# DoorBellRepeater.net
KiCad netlist of a schematic drawn in EAGLE
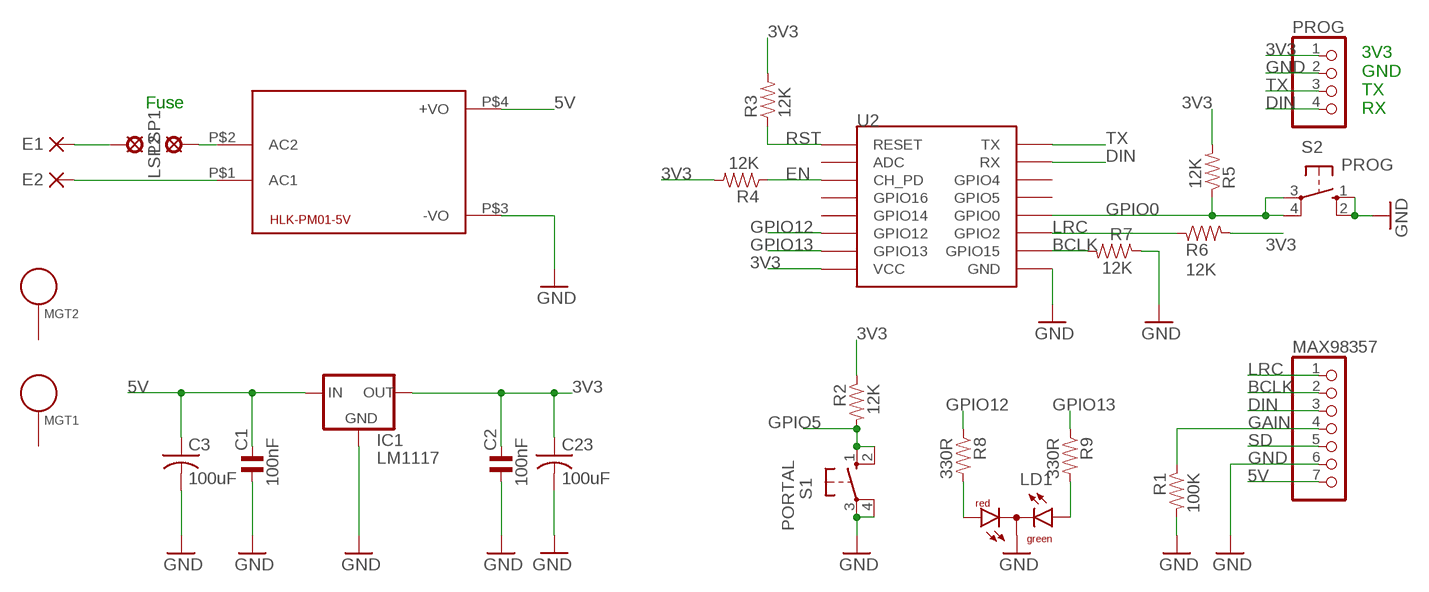
[diagram p0: schematic, sheet 1]

(export (version "E")
  (design (tool "Eeschema 10.0.6"))
  (components
    (comp (ref "C1")
      (value "100nF")
      (footprint "eagle-import:C0805MP")
      (libsource (lib "eagle-import") (part "C_0805MP"))
    )
    (comp (ref "C2")
      (value "100nF")
      (footprint "eagle-import:C0805MP")
      (libsource (lib "eagle-import") (part "C_0805MP"))
    )
    (comp (ref "C3")
      (value "100uF")
      (footprint "eagle-import:C0805K")
      (libsource (lib "eagle-import") (part "C-USC0805K"))
    )
    (comp (ref "C23")
      (value "100uF")
      (footprint "eagle-import:C0805K")
      (libsource (lib "eagle-import") (part "C-USC0805K"))
    )
    (comp (ref "E1")
      (value "PAD-0460S-S")
      (footprint "eagle-import:0460S-S")
      (libsource (lib "eagle-import") (part "PAD-0460S-S"))
    )
    (comp (ref "E2")
      (value "PAD-0460S-S")
      (footprint "eagle-import:0460S-S")
      (libsource (lib "eagle-import") (part "PAD-0460S-S"))
    )
    (comp (ref "HLK-PM01-5V")
      (value "HLK-PM013W")
      (footprint "eagle-import:HLK-PM01")
      (libsource (lib "eagle-import") (part "HLK-PM013W"))
    )
    (comp (ref "IC1")
      (value "LM1117")
      (footprint "eagle-import:SOT223")
      (libsource (lib "eagle-import") (part "LM1117"))
    )
    (comp (ref "LD1")
      (value "DUOLED-RG-C")
      (footprint "eagle-import:DUOLED-C-5MM")
      (libsource (lib "eagle-import") (part "DUOLED-RG-C"))
    )
    (comp (ref "LSP1")
      (value "LSP10")
      (footprint "eagle-import:LSP10")
      (libsource (lib "eagle-import") (part "LSP10"))
    )
    (comp (ref "LSP2")
      (value "LSP10")
      (footprint "eagle-import:LSP10")
      (libsource (lib "eagle-import") (part "LSP10"))
    )
    (comp (ref "MAX98357")
      (value "PINHD-1X7")
      (footprint "eagle-import:1X07")
      (libsource (lib "eagle-import") (part "PINHD-1X7"))
    )
    (comp (ref "MGT1")
      (value "MOUNTING_HOLE")
      (footprint "eagle-import:BEAGLEBONEBLACK_MOUNTING_HOLE")
      (libsource (lib "eagle-import") (part "MOUNTING_HOLE"))
    )
    (comp (ref "MGT2")
      (value "MOUNTING_HOLE")
      (footprint "eagle-import:BEAGLEBONEBLACK_MOUNTING_HOLE")
      (libsource (lib "eagle-import") (part "MOUNTING_HOLE"))
    )
    (comp (ref "PROG")
      (value "PINHD-1X4")
      (footprint "eagle-import:1X04")
      (libsource (lib "eagle-import") (part "PINHD-1X4"))
    )
    (comp (ref "R1")
      (value "100K")
      (footprint "eagle-import:0805_RES")
      (libsource (lib "eagle-import") (part "RESISTOR0805_RES"))
    )
    (comp (ref "R2")
      (value "12K")
      (footprint "eagle-import:0805_RES")
      (libsource (lib "eagle-import") (part "RESISTOR0805_RES"))
    )
    (comp (ref "R3")
      (value "12K")
      (footprint "eagle-import:0805_RES")
      (libsource (lib "eagle-import") (part "RESISTOR0805_RES"))
    )
    (comp (ref "R4")
      (value "12K")
      (footprint "eagle-import:0805_RES")
      (libsource (lib "eagle-import") (part "RESISTOR0805_RES"))
    )
    (comp (ref "R5")
      (value "12K")
      (footprint "eagle-import:0805_RES")
      (libsource (lib "eagle-import") (part "RESISTOR0805_RES"))
    )
    (comp (ref "R6")
      (value "12K")
      (footprint "eagle-import:0805_RES")
      (libsource (lib "eagle-import") (part "RESISTOR0805_RES"))
    )
    (comp (ref "R7")
      (value "12K")
      (footprint "eagle-import:0805_RES")
      (libsource (lib "eagle-import") (part "RESISTOR0805_RES"))
    )
    (comp (ref "R8")
      (value "330R")
      (footprint "eagle-import:0805_RES")
      (libsource (lib "eagle-import") (part "RESISTOR0805_RES"))
    )
    (comp (ref "R9")
      (value "330R")
      (footprint "eagle-import:0805_RES")
      (libsource (lib "eagle-import") (part "RESISTOR0805_RES"))
    )
    (comp (ref "S1")
      (value "PORTAL")
      (footprint "eagle-import:B3F-10XX")
      (fields (field (name "MPN") "B3F-1000"))
      (libsource (lib "eagle-import") (part "10-XX"))
    )
    (comp (ref "S2")
      (value "PROG")
      (footprint "eagle-import:B3F-10XX")
      (fields (field (name "MPN") "B3F-1000"))
      (libsource (lib "eagle-import") (part "10-XX"))
    )
    (comp (ref "U2")
      (value "ESP12")
      (footprint "eagle-import:ESP12")
      (libsource (lib "eagle-import") (part "ESP12"))
    )
  )
  (nets
    (net (code "1") (name "/3V3") (class "Default")
      (node (ref "C2") (pin "2") (pinfunction "2_2") (pintype "passive"))
      (node (ref "C23") (pin "1") (pinfunction "1_1") (pintype "passive"))
      (node (ref "IC1") (pin "2") (pinfunction "OUT_2") (pintype "passive"))
      (node (ref "PROG") (pin "1") (pinfunction "1_1") (pintype "passive"))
      (node (ref "R2") (pin "1") (pinfunction "1_1") (pintype "passive"))
      (node (ref "R3") (pin "2") (pinfunction "2_2") (pintype "passive"))
      (node (ref "R4") (pin "2") (pinfunction "2_2") (pintype "passive"))
      (node (ref "R5") (pin "2") (pinfunction "2_2") (pintype "passive"))
      (node (ref "R6") (pin "2") (pinfunction "2_2") (pintype "passive"))
      (node (ref "U2") (pin "VCC") (pinfunction "VCC_VCC") (pintype "bidirectional"))
    )
    (net (code "2") (name "/5V") (class "Default")
      (node (ref "C1") (pin "2") (pinfunction "2_2") (pintype "passive"))
      (node (ref "C3") (pin "1") (pinfunction "1_1") (pintype "passive"))
      (node (ref "HLK-PM01-5V") (pin "P$4") (pinfunction "+VO_P$4") (pintype "bidirectional"))
      (node (ref "IC1") (pin "3") (pinfunction "IN_3") (pintype "input"))
      (node (ref "MAX98357") (pin "7") (pinfunction "7_7") (pintype "passive"))
    )
    (net (code "3") (name "/BCLK") (class "Default")
      (node (ref "MAX98357") (pin "2") (pinfunction "2_2") (pintype "passive"))
      (node (ref "R7") (pin "2") (pinfunction "2_2") (pintype "passive"))
      (node (ref "U2") (pin "GPIO15") (pinfunction "GPIO15_GPIO15") (pintype "bidirectional"))
    )
    (net (code "4") (name "/DIN") (class "Default")
      (node (ref "MAX98357") (pin "3") (pinfunction "3_3") (pintype "passive"))
      (node (ref "PROG") (pin "4") (pinfunction "4_4") (pintype "passive"))
      (node (ref "U2") (pin "RX") (pinfunction "RX_RX") (pintype "bidirectional"))
    )
    (net (code "5") (name "/EN") (class "Default")
      (node (ref "R4") (pin "1") (pinfunction "1_1") (pintype "passive"))
      (node (ref "U2") (pin "CH_PD") (pinfunction "CH_PD_CH_PD") (pintype "bidirectional"))
    )
    (net (code "6") (name "/GAIN") (class "Default")
      (node (ref "MAX98357") (pin "4") (pinfunction "4_4") (pintype "passive"))
      (node (ref "R1") (pin "1") (pinfunction "1_1") (pintype "passive"))
    )
    (net (code "7") (name "/GPIO0") (class "Default")
      (node (ref "R5") (pin "1") (pinfunction "1_1") (pintype "passive"))
      (node (ref "S2") (pin "3") (pinfunction "P_3") (pintype "passive"))
      (node (ref "S2") (pin "4") (pinfunction "P1_4") (pintype "passive"))
      (node (ref "U2") (pin "GPIO0") (pinfunction "GPIO0_GPIO0") (pintype "bidirectional"))
    )
    (net (code "8") (name "/GPIO5") (class "Default")
      (node (ref "R2") (pin "2") (pinfunction "2_2") (pintype "passive"))
      (node (ref "S1") (pin "1") (pinfunction "S_1") (pintype "passive"))
      (node (ref "S1") (pin "2") (pinfunction "S1_2") (pintype "passive"))
    )
    (net (code "9") (name "/GPIO12") (class "Default")
      (node (ref "R8") (pin "1") (pinfunction "1_1") (pintype "passive"))
      (node (ref "U2") (pin "GPIO12") (pinfunction "GPIO12_GPIO12") (pintype "bidirectional"))
    )
    (net (code "10") (name "/GPIO13") (class "Default")
      (node (ref "R9") (pin "1") (pinfunction "1_1") (pintype "passive"))
      (node (ref "U2") (pin "GPIO13") (pinfunction "GPIO13_GPIO13") (pintype "bidirectional"))
    )
    (net (code "11") (name "/LRC") (class "Default")
      (node (ref "MAX98357") (pin "1") (pinfunction "1_1") (pintype "passive"))
      (node (ref "R6") (pin "1") (pinfunction "1_1") (pintype "passive"))
      (node (ref "U2") (pin "GPIO2") (pinfunction "GPIO2_GPIO2") (pintype "bidirectional"))
    )
    (net (code "12") (name "/RST") (class "Default")
      (node (ref "R3") (pin "1") (pinfunction "1_1") (pintype "passive"))
      (node (ref "U2") (pin "RESET") (pinfunction "RESET_RESET") (pintype "bidirectional"))
    )
    (net (code "13") (name "/SD") (class "Default")
      (node (ref "MAX98357") (pin "5") (pinfunction "5_5") (pintype "passive"))
    )
    (net (code "14") (name "/TX") (class "Default")
      (node (ref "PROG") (pin "3") (pinfunction "3_3") (pintype "passive"))
      (node (ref "U2") (pin "TX") (pinfunction "TX_TX") (pintype "bidirectional"))
    )
    (net (code "15") (name "GND") (class "Default")
      (node (ref "C1") (pin "1") (pinfunction "1_1") (pintype "passive"))
      (node (ref "C2") (pin "1") (pinfunction "1_1") (pintype "passive"))
      (node (ref "C23") (pin "2") (pinfunction "2_2") (pintype "passive"))
      (node (ref "C3") (pin "2") (pinfunction "2_2") (pintype "passive"))
      (node (ref "HLK-PM01-5V") (pin "P$3") (pinfunction "-VO_P$3") (pintype "bidirectional"))
      (node (ref "IC1") (pin "1") (pinfunction "GND_1") (pintype "input"))
      (node (ref "LD1") (pin "C") (pinfunction "C_C") (pintype "passive"))
      (node (ref "MAX98357") (pin "6") (pinfunction "6_6") (pintype "passive"))
      (node (ref "PROG") (pin "2") (pinfunction "2_2") (pintype "passive"))
      (node (ref "R1") (pin "2") (pinfunction "2_2") (pintype "passive"))
      (node (ref "R7") (pin "1") (pinfunction "1_1") (pintype "passive"))
      (node (ref "S1") (pin "3") (pinfunction "P_3") (pintype "passive"))
      (node (ref "S1") (pin "4") (pinfunction "P1_4") (pintype "passive"))
      (node (ref "S2") (pin "1") (pinfunction "S_1") (pintype "passive"))
      (node (ref "S2") (pin "2") (pinfunction "S1_2") (pintype "passive"))
      (node (ref "U2") (pin "GND") (pinfunction "GND_GND") (pintype "bidirectional"))
    )
    (net (code "16") (name "Net-(E1-P)") (class "Default")
      (node (ref "E1") (pin "1") (pinfunction "P_1") (pintype "passive"))
      (node (ref "LSP2") (pin "MP") (pinfunction "MP_MP") (pintype "passive"))
    )
    (net (code "17") (name "Net-(E2-P)") (class "Default")
      (node (ref "E2") (pin "1") (pinfunction "P_1") (pintype "passive"))
      (node (ref "HLK-PM01-5V") (pin "P$1") (pinfunction "AC1_P$1") (pintype "bidirectional"))
    )
    (net (code "18") (name "Net-(HLK-PM01-5V-AC2)") (class "Default")
      (node (ref "HLK-PM01-5V") (pin "P$2") (pinfunction "AC2_P$2") (pintype "bidirectional"))
      (node (ref "LSP1") (pin "MP") (pinfunction "MP_MP") (pintype "passive"))
    )
    (net (code "19") (name "Net-(LD1-AG)") (class "Default")
      (node (ref "LD1") (pin "AX") (pinfunction "AG_AX") (pintype "passive"))
      (node (ref "R9") (pin "2") (pinfunction "2_2") (pintype "passive"))
    )
    (net (code "20") (name "Net-(LD1-PadAR)") (class "Default")
      (node (ref "LD1") (pin "AR") (pinfunction "AR_AR") (pintype "passive"))
      (node (ref "R8") (pin "2") (pinfunction "2_2") (pintype "passive"))
    )
    (net (code "21") (name "unconnected-(MGT1-PadP$1)") (class "Default")
      (node (ref "MGT1") (pin "P$1") (pinfunction "P$1_P$1") (pintype "bidirectional"))
    )
    (net (code "22") (name "unconnected-(MGT2-PadP$1)") (class "Default")
      (node (ref "MGT2") (pin "P$1") (pinfunction "P$1_P$1") (pintype "bidirectional"))
    )
    (net (code "23") (name "unconnected-(U2-PadADC)") (class "Default")
      (node (ref "U2") (pin "ADC") (pinfunction "ADC_ADC") (pintype "bidirectional"))
    )
    (net (code "24") (name "unconnected-(U2-PadGPIO4)") (class "Default")
      (node (ref "U2") (pin "GPIO4") (pinfunction "GPIO4_GPIO4") (pintype "bidirectional"))
    )
    (net (code "25") (name "unconnected-(U2-PadGPIO5)") (class "Default")
      (node (ref "U2") (pin "GPIO5") (pinfunction "GPIO5_GPIO5") (pintype "bidirectional"))
    )
    (net (code "26") (name "unconnected-(U2-PadGPIO14)") (class "Default")
      (node (ref "U2") (pin "GPIO14") (pinfunction "GPIO14_GPIO14") (pintype "bidirectional"))
    )
    (net (code "27") (name "unconnected-(U2-PadGPIO16)") (class "Default")
      (node (ref "U2") (pin "GPIO16") (pinfunction "GPIO16_GPIO16") (pintype "bidirectional"))
    )
  )
)
